# POWER_USB_UART.net
KiCad netlist of a schematic drawn in Altium Designer
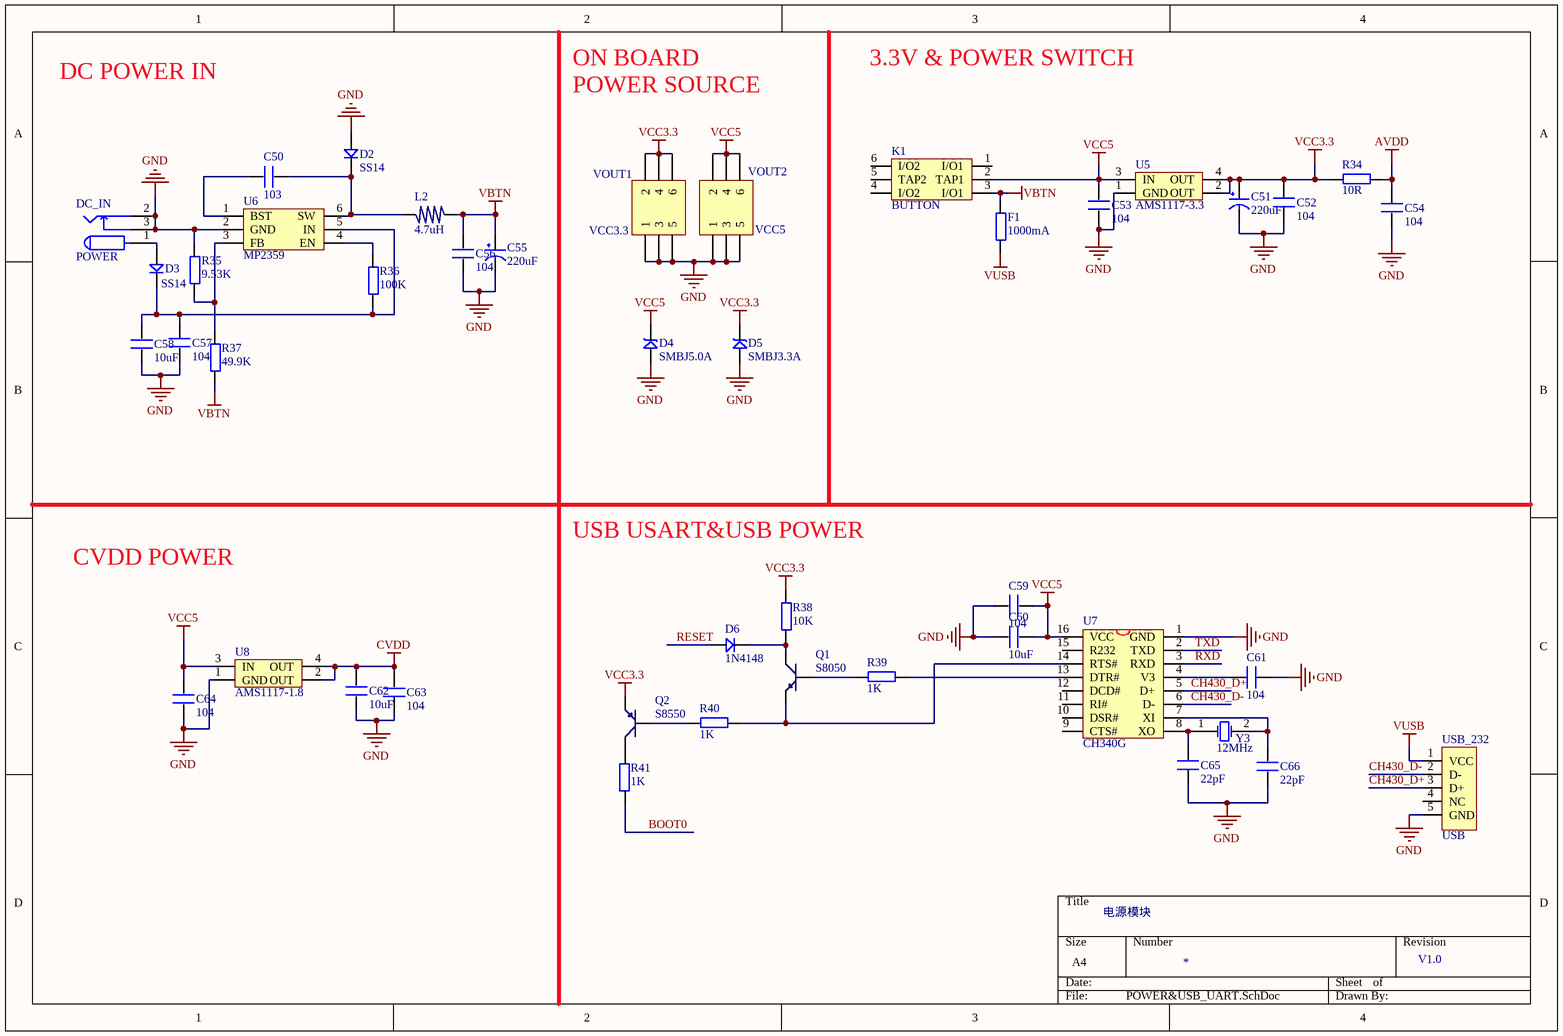
[diagram p0: POWER&USB_UART.SchDoc]

(export (version "E")
  (design (tool "Eeschema 10.0.6"))
  (components
    (comp (ref "C50") (value "103") (footprint "0603P") (libsource (lib "WarShip V3 STM32103封装库") (part "C")))
    (comp (ref "C51")
      (value "220uF")
      (footprint "CC6.56.5")
      (libsource (lib "WarShip V3 STM32103封装库") (part "CAP"))
    )
    (comp (ref "C52") (value "104") (footprint "0603P") (libsource (lib "WarShip V3 STM32103封装库") (part "C")))
    (comp (ref "C53") (value "104") (footprint "0603P") (libsource (lib "WarShip V3 STM32103封装库") (part "C")))
    (comp (ref "C54") (value "104") (footprint "0603P") (libsource (lib "WarShip V3 STM32103封装库") (part "C")))
    (comp (ref "C55")
      (value "220uF")
      (footprint "CC6.56.5")
      (libsource (lib "WarShip V3 STM32103封装库") (part "CAP"))
    )
    (comp (ref "C56") (value "104") (footprint "0603P") (libsource (lib "WarShip V3 STM32103封装库") (part "C")))
    (comp (ref "C57") (value "104") (footprint "0603P") (libsource (lib "WarShip V3 STM32103封装库") (part "C")))
    (comp (ref "C58")
      (value "10uF")
      (footprint "0603P")
      (libsource (lib "WarShip V3 STM32103封装库") (part "C"))
    )
    (comp (ref "C59") (value "104") (footprint "0603P") (libsource (lib "WarShip V3 STM32103封装库") (part "C")))
    (comp (ref "C60")
      (value "10uF")
      (footprint "0603P")
      (libsource (lib "WarShip V3 STM32103封装库") (part "C"))
    )
    (comp (ref "C61") (value "104") (footprint "0603P") (libsource (lib "WarShip V3 STM32103封装库") (part "C")))
    (comp (ref "C62")
      (value "10uF")
      (footprint "0603P")
      (libsource (lib "WarShip V3 STM32103封装库") (part "C"))
    )
    (comp (ref "C63") (value "104") (footprint "0603P") (libsource (lib "WarShip V3 STM32103封装库") (part "C")))
    (comp (ref "C64") (value "104") (footprint "0603P") (libsource (lib "WarShip V3 STM32103封装库") (part "C")))
    (comp (ref "C65")
      (value "22pF")
      (footprint "0603P")
      (libsource (lib "WarShip V3 STM32103封装库") (part "C"))
    )
    (comp (ref "C66")
      (value "22pF")
      (footprint "0603P")
      (libsource (lib "WarShip V3 STM32103封装库") (part "C"))
    )
    (comp (ref "D2")
      (value "SS14")
      (footprint "DIODE_3*5.3")
      (libsource (lib "WarShip V3 STM32103封装库") (part "D"))
    )
    (comp (ref "D3")
      (value "SS14")
      (footprint "DIODE_3*5.3")
      (libsource (lib "WarShip V3 STM32103封装库") (part "D"))
    )
    (comp (ref "D4")
      (value "SMBJ5.0A")
      (footprint "SMBJ")
      (description "TVS")
      (libsource (lib "WarShip V3 STM32103封装库") (part "SMBJ"))
    )
    (comp (ref "D5")
      (value "SMBJ3.3A")
      (footprint "SMBJ")
      (description "TVS")
      (libsource (lib "WarShip V3 STM32103封装库") (part "SMBJ"))
    )
    (comp (ref "D6")
      (value "1N4148")
      (footprint "DIODE_SOP")
      (libsource (lib "WarShip V3 STM32103封装库") (part "D"))
    )
    (comp (ref "DC_IN")
      (value "POWER")
      (footprint "DC10B")
      (libsource (lib "WarShip V3 STM32103封装库") (part "POW"))
    )
    (comp (ref "F1")
      (value "1000mA")
      (footprint "1206")
      (libsource (lib "WarShip V3 STM32103封装库") (part "R"))
    )
    (comp (ref "K1")
      (value "BUTTON")
      (footprint "BTN8.5*8.5")
      (libsource (lib "WarShip V3 STM32103封装库") (part "BUTTON"))
    )
    (comp (ref "L2")
      (value "4.7uH")
      (footprint "L_SOP74")
      (libsource (lib "WarShip V3 STM32103封装库") (part "L"))
    )
    (comp (ref "Q1")
      (value "S8050")
      (footprint "SOT-23R")
      (description "8050/BCW846/BCW847")
      (libsource (lib "WarShip V3 STM32103封装库") (part "NPN"))
    )
    (comp (ref "Q2")
      (value "S8550")
      (footprint "SOT-23R")
      (description "8550/BCW68")
      (libsource (lib "WarShip V3 STM32103封装库") (part "PNP"))
    )
    (comp (ref "R34") (value "10R") (footprint "0603P") (libsource (lib "WarShip V3 STM32103封装库") (part "R")))
    (comp (ref "R35")
      (value "9.53K")
      (footprint "0603P")
      (libsource (lib "WarShip V3 STM32103封装库") (part "R"))
    )
    (comp (ref "R36")
      (value "100K")
      (footprint "0603P")
      (libsource (lib "WarShip V3 STM32103封装库") (part "R"))
    )
    (comp (ref "R37")
      (value "49.9K")
      (footprint "0603P")
      (libsource (lib "WarShip V3 STM32103封装库") (part "R"))
    )
    (comp (ref "R38") (value "10K") (footprint "0603P") (libsource (lib "WarShip V3 STM32103封装库") (part "R")))
    (comp (ref "R39") (value "1K") (footprint "0603P") (libsource (lib "WarShip V3 STM32103封装库") (part "R")))
    (comp (ref "R40") (value "1K") (footprint "0603P") (libsource (lib "WarShip V3 STM32103封装库") (part "R")))
    (comp (ref "R41") (value "1K") (footprint "0603P") (libsource (lib "WarShip V3 STM32103封装库") (part "R")))
    (comp (ref "U5")
      (value "AMS1117-3.3")
      (footprint "AMS1117")
      (libsource (lib "WarShip V3 STM32103封装库") (part "AMS1117"))
    )
    (comp (ref "U6")
      (value "MP2359")
      (footprint "SOT-23-6")
      (description "DC DC Step Down IC")
      (libsource (lib "WarShip V3 STM32103封装库") (part "MP2359"))
    )
    (comp (ref "U7")
      (value "CH340G")
      (footprint "SOP16M")
      (description "USB2UART")
      (libsource (lib "WarShip V3 STM32103封装库") (part "CH340G"))
    )
    (comp (ref "U8")
      (value "AMS1117-1.8")
      (footprint "AMS1117")
      (libsource (lib "WarShip V3 STM32103封装库") (part "AMS1117"))
    )
    (comp (ref "USB_232")
      (value "USB")
      (footprint "USB/SM0.8-6H5")
      (libsource (lib "WarShip V3 STM32103封装库") (part "USB5"))
    )
    (comp (ref "VOUT1")
      (value "VCC3.3")
      (footprint "HDR2X3")
      (description "Header, 3-Pin, Dual row")
      (fields (field (name "PUBLISHER") "Altium Limited"))
      (libsource (lib "WarShip V3 STM32103封装库") (part "Header 3X2"))
    )
    (comp (ref "VOUT2")
      (value "VCC5")
      (footprint "HDR2X3")
      (description "Header, 3-Pin, Dual row")
      (fields (field (name "PUBLISHER") "Altium Limited"))
      (libsource (lib "WarShip V3 STM32103封装库") (part "Header 3X2"))
    )
    (comp (ref "Y3")
      (value "12MHz")
      (footprint "XTAL_US")
      (description "Crystal Oscillator")
      (fields (field (name "PUBLISHER") "Altium Limited"))
      (libsource (lib "WarShip V3 STM32103封装库") (part "XTAL"))
    )
  )
  (nets
    (net (code "1") (name "/BOOT0") (class "Default") (node (ref "R41") (pin "2") (pintype "passive")))
    (net (code "2") (name "/CH430_D+") (class "Default")
      (node (ref "U7") (pin "5") (pinfunction "D+_5") (pintype "passive"))
      (node (ref "USB_232") (pin "3") (pinfunction "D+_3") (pintype "passive"))
    )
    (net (code "3") (name "/CH430_D-") (class "Default")
      (node (ref "U7") (pin "6") (pinfunction "D-_6") (pintype "passive"))
      (node (ref "USB_232") (pin "2") (pinfunction "D-_2") (pintype "passive"))
    )
    (net (code "4") (name "/RESET") (class "Default") (node (ref "D6") (pin "1") (pintype "passive")))
    (net (code "5") (name "/RXD") (class "Default")
      (node (ref "U7") (pin "3") (pinfunction "RXD_3") (pintype "passive"))
    )
    (net (code "6") (name "/TXD") (class "Default")
      (node (ref "U7") (pin "2") (pinfunction "TXD_2") (pintype "passive"))
    )
    (net (code "7") (name "AVDD") (class "Default")
      (node (ref "C54") (pin "2") (pintype "passive"))
      (node (ref "R34") (pin "1") (pintype "passive"))
    )
    (net (code "8") (name "CVDD") (class "Default")
      (node (ref "C62") (pin "2") (pintype "passive"))
      (node (ref "C63") (pin "2") (pintype "passive"))
      (node (ref "U8") (pin "2") (pinfunction "OUT_2") (pintype "passive"))
      (node (ref "U8") (pin "4") (pinfunction "OUT_4") (pintype "passive"))
    )
    (net (code "9") (name "GND") (class "Default")
      (node (ref "C51") (pin "2") (pinfunction "GND_2") (pintype "passive"))
      (node (ref "C52") (pin "1") (pintype "passive"))
      (node (ref "C53") (pin "1") (pintype "passive"))
      (node (ref "C54") (pin "1") (pintype "passive"))
      (node (ref "C55") (pin "2") (pinfunction "GND_2") (pintype "passive"))
      (node (ref "C56") (pin "1") (pintype "passive"))
      (node (ref "C57") (pin "1") (pintype "passive"))
      (node (ref "C58") (pin "1") (pintype "passive"))
      (node (ref "C59") (pin "2") (pintype "passive"))
      (node (ref "C60") (pin "2") (pintype "passive"))
      (node (ref "C61") (pin "1") (pintype "passive"))
      (node (ref "C62") (pin "1") (pintype "passive"))
      (node (ref "C63") (pin "1") (pintype "passive"))
      (node (ref "C64") (pin "1") (pintype "passive"))
      (node (ref "C65") (pin "2") (pintype "passive"))
      (node (ref "C66") (pin "2") (pintype "passive"))
      (node (ref "D2") (pin "1") (pintype "passive"))
      (node (ref "D4") (pin "1") (pintype "passive"))
      (node (ref "D5") (pin "1") (pintype "passive"))
      (node (ref "DC_IN") (pin "2") (pintype "passive"))
      (node (ref "DC_IN") (pin "3") (pintype "passive"))
      (node (ref "R35") (pin "2") (pintype "passive"))
      (node (ref "U5") (pin "1") (pinfunction "GND_1") (pintype "passive"))
      (node (ref "U6") (pin "2") (pinfunction "GND_2") (pintype "passive"))
      (node (ref "U7") (pin "1") (pinfunction "GND_1") (pintype "passive"))
      (node (ref "U8") (pin "1") (pinfunction "GND_1") (pintype "passive"))
      (node (ref "USB_232") (pin "5") (pinfunction "GND_5") (pintype "passive"))
      (node (ref "VOUT1") (pin "1") (pinfunction "1_1") (pintype "passive"))
      (node (ref "VOUT1") (pin "3") (pinfunction "3_3") (pintype "passive"))
      (node (ref "VOUT1") (pin "5") (pinfunction "5_5") (pintype "passive"))
      (node (ref "VOUT2") (pin "1") (pinfunction "1_1") (pintype "passive"))
      (node (ref "VOUT2") (pin "3") (pinfunction "3_3") (pintype "passive"))
      (node (ref "VOUT2") (pin "5") (pinfunction "5_5") (pintype "passive"))
    )
    (net (code "10") (name "Net-(D3-Pad1)") (class "Default")
      (node (ref "D3") (pin "1") (pintype "passive"))
      (node (ref "DC_IN") (pin "1") (pintype "passive"))
    )
    (net (code "11") (name "Net-(Q1-B)") (class "Default")
      (node (ref "Q1") (pin "2") (pinfunction "B_2") (pintype "passive"))
      (node (ref "R39") (pin "2") (pintype "passive"))
    )
    (net (code "12") (name "Net-(Q1-C)") (class "Default")
      (node (ref "D6") (pin "2") (pintype "passive"))
      (node (ref "Q1") (pin "3") (pinfunction "C_3") (pintype "passive"))
      (node (ref "R38") (pin "1") (pintype "passive"))
    )
    (net (code "13") (name "Net-(Q1-E)") (class "Default")
      (node (ref "Q1") (pin "1") (pinfunction "E_1") (pintype "passive"))
      (node (ref "R40") (pin "1") (pintype "passive"))
      (node (ref "U7") (pin "14") (pinfunction "RTS#_14") (pintype "passive"))
    )
    (net (code "14") (name "Net-(Q2-B)") (class "Default")
      (node (ref "Q2") (pin "2") (pinfunction "B_2") (pintype "passive"))
      (node (ref "R40") (pin "2") (pintype "passive"))
    )
    (net (code "15") (name "Net-(Q2-C)") (class "Default")
      (node (ref "Q2") (pin "3") (pinfunction "C_3") (pintype "passive"))
      (node (ref "R41") (pin "1") (pintype "passive"))
    )
    (net (code "16") (name "Net-(U6-BST)") (class "Default")
      (node (ref "C50") (pin "1") (pintype "passive"))
      (node (ref "U6") (pin "1") (pinfunction "BST_1") (pintype "passive"))
    )
    (net (code "17") (name "Net-(U6-EN)") (class "Default")
      (node (ref "R36") (pin "2") (pintype "passive"))
      (node (ref "U6") (pin "4") (pinfunction "EN_4") (pintype "passive"))
    )
    (net (code "18") (name "Net-(U6-FB)") (class "Default")
      (node (ref "R35") (pin "1") (pintype "passive"))
      (node (ref "R37") (pin "2") (pintype "passive"))
      (node (ref "U6") (pin "3") (pinfunction "FB_3") (pintype "passive"))
    )
    (net (code "19") (name "Net-(U6-IN)") (class "Default")
      (node (ref "C57") (pin "2") (pintype "passive"))
      (node (ref "C58") (pin "2") (pintype "passive"))
      (node (ref "D3") (pin "2") (pintype "passive"))
      (node (ref "R36") (pin "1") (pintype "passive"))
      (node (ref "U6") (pin "5") (pinfunction "IN_5") (pintype "passive"))
    )
    (net (code "20") (name "Net-(U6-SW)") (class "Default")
      (node (ref "C50") (pin "2") (pintype "passive"))
      (node (ref "D2") (pin "2") (pintype "passive"))
      (node (ref "L2") (pin "1") (pintype "passive"))
      (node (ref "U6") (pin "6") (pinfunction "SW_6") (pintype "passive"))
    )
    (net (code "21") (name "Net-(U7-DTR#)") (class "Default")
      (node (ref "R39") (pin "1") (pintype "passive"))
      (node (ref "U7") (pin "13") (pinfunction "DTR#_13") (pintype "passive"))
    )
    (net (code "22") (name "Net-(U7-V3)") (class "Default")
      (node (ref "C61") (pin "2") (pintype "passive"))
      (node (ref "U7") (pin "4") (pinfunction "V3_4") (pintype "passive"))
    )
    (net (code "23") (name "Net-(U7-XI)") (class "Default")
      (node (ref "C66") (pin "1") (pintype "passive"))
      (node (ref "U7") (pin "7") (pinfunction "XI_7") (pintype "passive"))
      (node (ref "Y3") (pin "2") (pinfunction "OSC2_2") (pintype "passive"))
    )
    (net (code "24") (name "Net-(U7-XO)") (class "Default")
      (node (ref "C65") (pin "1") (pintype "passive"))
      (node (ref "U7") (pin "8") (pinfunction "XO_8") (pintype "passive"))
      (node (ref "Y3") (pin "1") (pinfunction "OSC1_1") (pintype "passive"))
    )
    (net (code "25") (name "VBTN") (class "Default")
      (node (ref "C55") (pin "1") (pinfunction "VCC_1") (pintype "passive"))
      (node (ref "C56") (pin "2") (pintype "passive"))
      (node (ref "F1") (pin "2") (pintype "passive"))
      (node (ref "K1") (pin "3") (pinfunction "I/O1_3") (pintype "passive"))
      (node (ref "L2") (pin "2") (pintype "passive"))
      (node (ref "R37") (pin "1") (pintype "passive"))
    )
    (net (code "26") (name "VCC3.3") (class "Default")
      (node (ref "C51") (pin "1") (pinfunction "VCC_1") (pintype "passive"))
      (node (ref "C52") (pin "2") (pintype "passive"))
      (node (ref "D5") (pin "2") (pintype "passive"))
      (node (ref "Q2") (pin "1") (pinfunction "E_1") (pintype "passive"))
      (node (ref "R34") (pin "2") (pintype "passive"))
      (node (ref "R38") (pin "2") (pintype "passive"))
      (node (ref "U5") (pin "2") (pinfunction "OUT_2") (pintype "passive"))
      (node (ref "U5") (pin "4") (pinfunction "OUT_4") (pintype "passive"))
      (node (ref "VOUT1") (pin "2") (pinfunction "2_2") (pintype "passive"))
      (node (ref "VOUT1") (pin "4") (pinfunction "4_4") (pintype "passive"))
      (node (ref "VOUT1") (pin "6") (pinfunction "6_6") (pintype "passive"))
    )
    (net (code "27") (name "VCC5") (class "Default")
      (node (ref "C53") (pin "2") (pintype "passive"))
      (node (ref "C59") (pin "1") (pintype "passive"))
      (node (ref "C60") (pin "1") (pintype "passive"))
      (node (ref "C64") (pin "2") (pintype "passive"))
      (node (ref "D4") (pin "2") (pintype "passive"))
      (node (ref "K1") (pin "2") (pinfunction "TAP1_2") (pintype "passive"))
      (node (ref "U5") (pin "3") (pinfunction "IN_3") (pintype "passive"))
      (node (ref "U7") (pin "16") (pinfunction "VCC_16") (pintype "passive"))
      (node (ref "U8") (pin "3") (pinfunction "IN_3") (pintype "passive"))
      (node (ref "VOUT2") (pin "2") (pinfunction "2_2") (pintype "passive"))
      (node (ref "VOUT2") (pin "4") (pinfunction "4_4") (pintype "passive"))
      (node (ref "VOUT2") (pin "6") (pinfunction "6_6") (pintype "passive"))
    )
    (net (code "28") (name "VUSB") (class "Default")
      (node (ref "F1") (pin "1") (pintype "passive"))
      (node (ref "USB_232") (pin "1") (pinfunction "VCC_1") (pintype "passive"))
    )
    (net (code "29") (name "unconnected-(K1-I{slash}O1-Pad1)") (class "Default")
      (node (ref "K1") (pin "1") (pinfunction "I/O1_1") (pintype "passive"))
    )
    (net (code "30") (name "unconnected-(K1-I{slash}O2-Pad4)") (class "Default")
      (node (ref "K1") (pin "4") (pinfunction "I/O2_4") (pintype "passive"))
    )
    (net (code "31") (name "unconnected-(K1-I{slash}O2-Pad6)") (class "Default")
      (node (ref "K1") (pin "6") (pinfunction "I/O2_6") (pintype "passive"))
    )
    (net (code "32") (name "unconnected-(K1-TAP2-Pad5)") (class "Default")
      (node (ref "K1") (pin "5") (pinfunction "TAP2_5") (pintype "passive"))
    )
    (net (code "33") (name "unconnected-(U7-CTS#-Pad9)") (class "Default")
      (node (ref "U7") (pin "9") (pinfunction "CTS#_9") (pintype "passive"))
    )
    (net (code "34") (name "unconnected-(U7-DCD#-Pad12)") (class "Default")
      (node (ref "U7") (pin "12") (pinfunction "DCD#_12") (pintype "passive"))
    )
    (net (code "35") (name "unconnected-(U7-DSR#-Pad10)") (class "Default")
      (node (ref "U7") (pin "10") (pinfunction "DSR#_10") (pintype "passive"))
    )
    (net (code "36") (name "unconnected-(U7-R232-Pad15)") (class "Default")
      (node (ref "U7") (pin "15") (pinfunction "R232_15") (pintype "passive"))
    )
    (net (code "37") (name "unconnected-(U7-RI#-Pad11)") (class "Default")
      (node (ref "U7") (pin "11") (pinfunction "RI#_11") (pintype "passive"))
    )
    (net (code "38") (name "unconnected-(USB_232-NC-Pad4)") (class "Default")
      (node (ref "USB_232") (pin "4") (pinfunction "NC_4") (pintype "passive"))
    )
  )
)
